# HVSUP_ISOL_Mainboard.net
KiCad netlist of a schematic drawn in Altium Designer
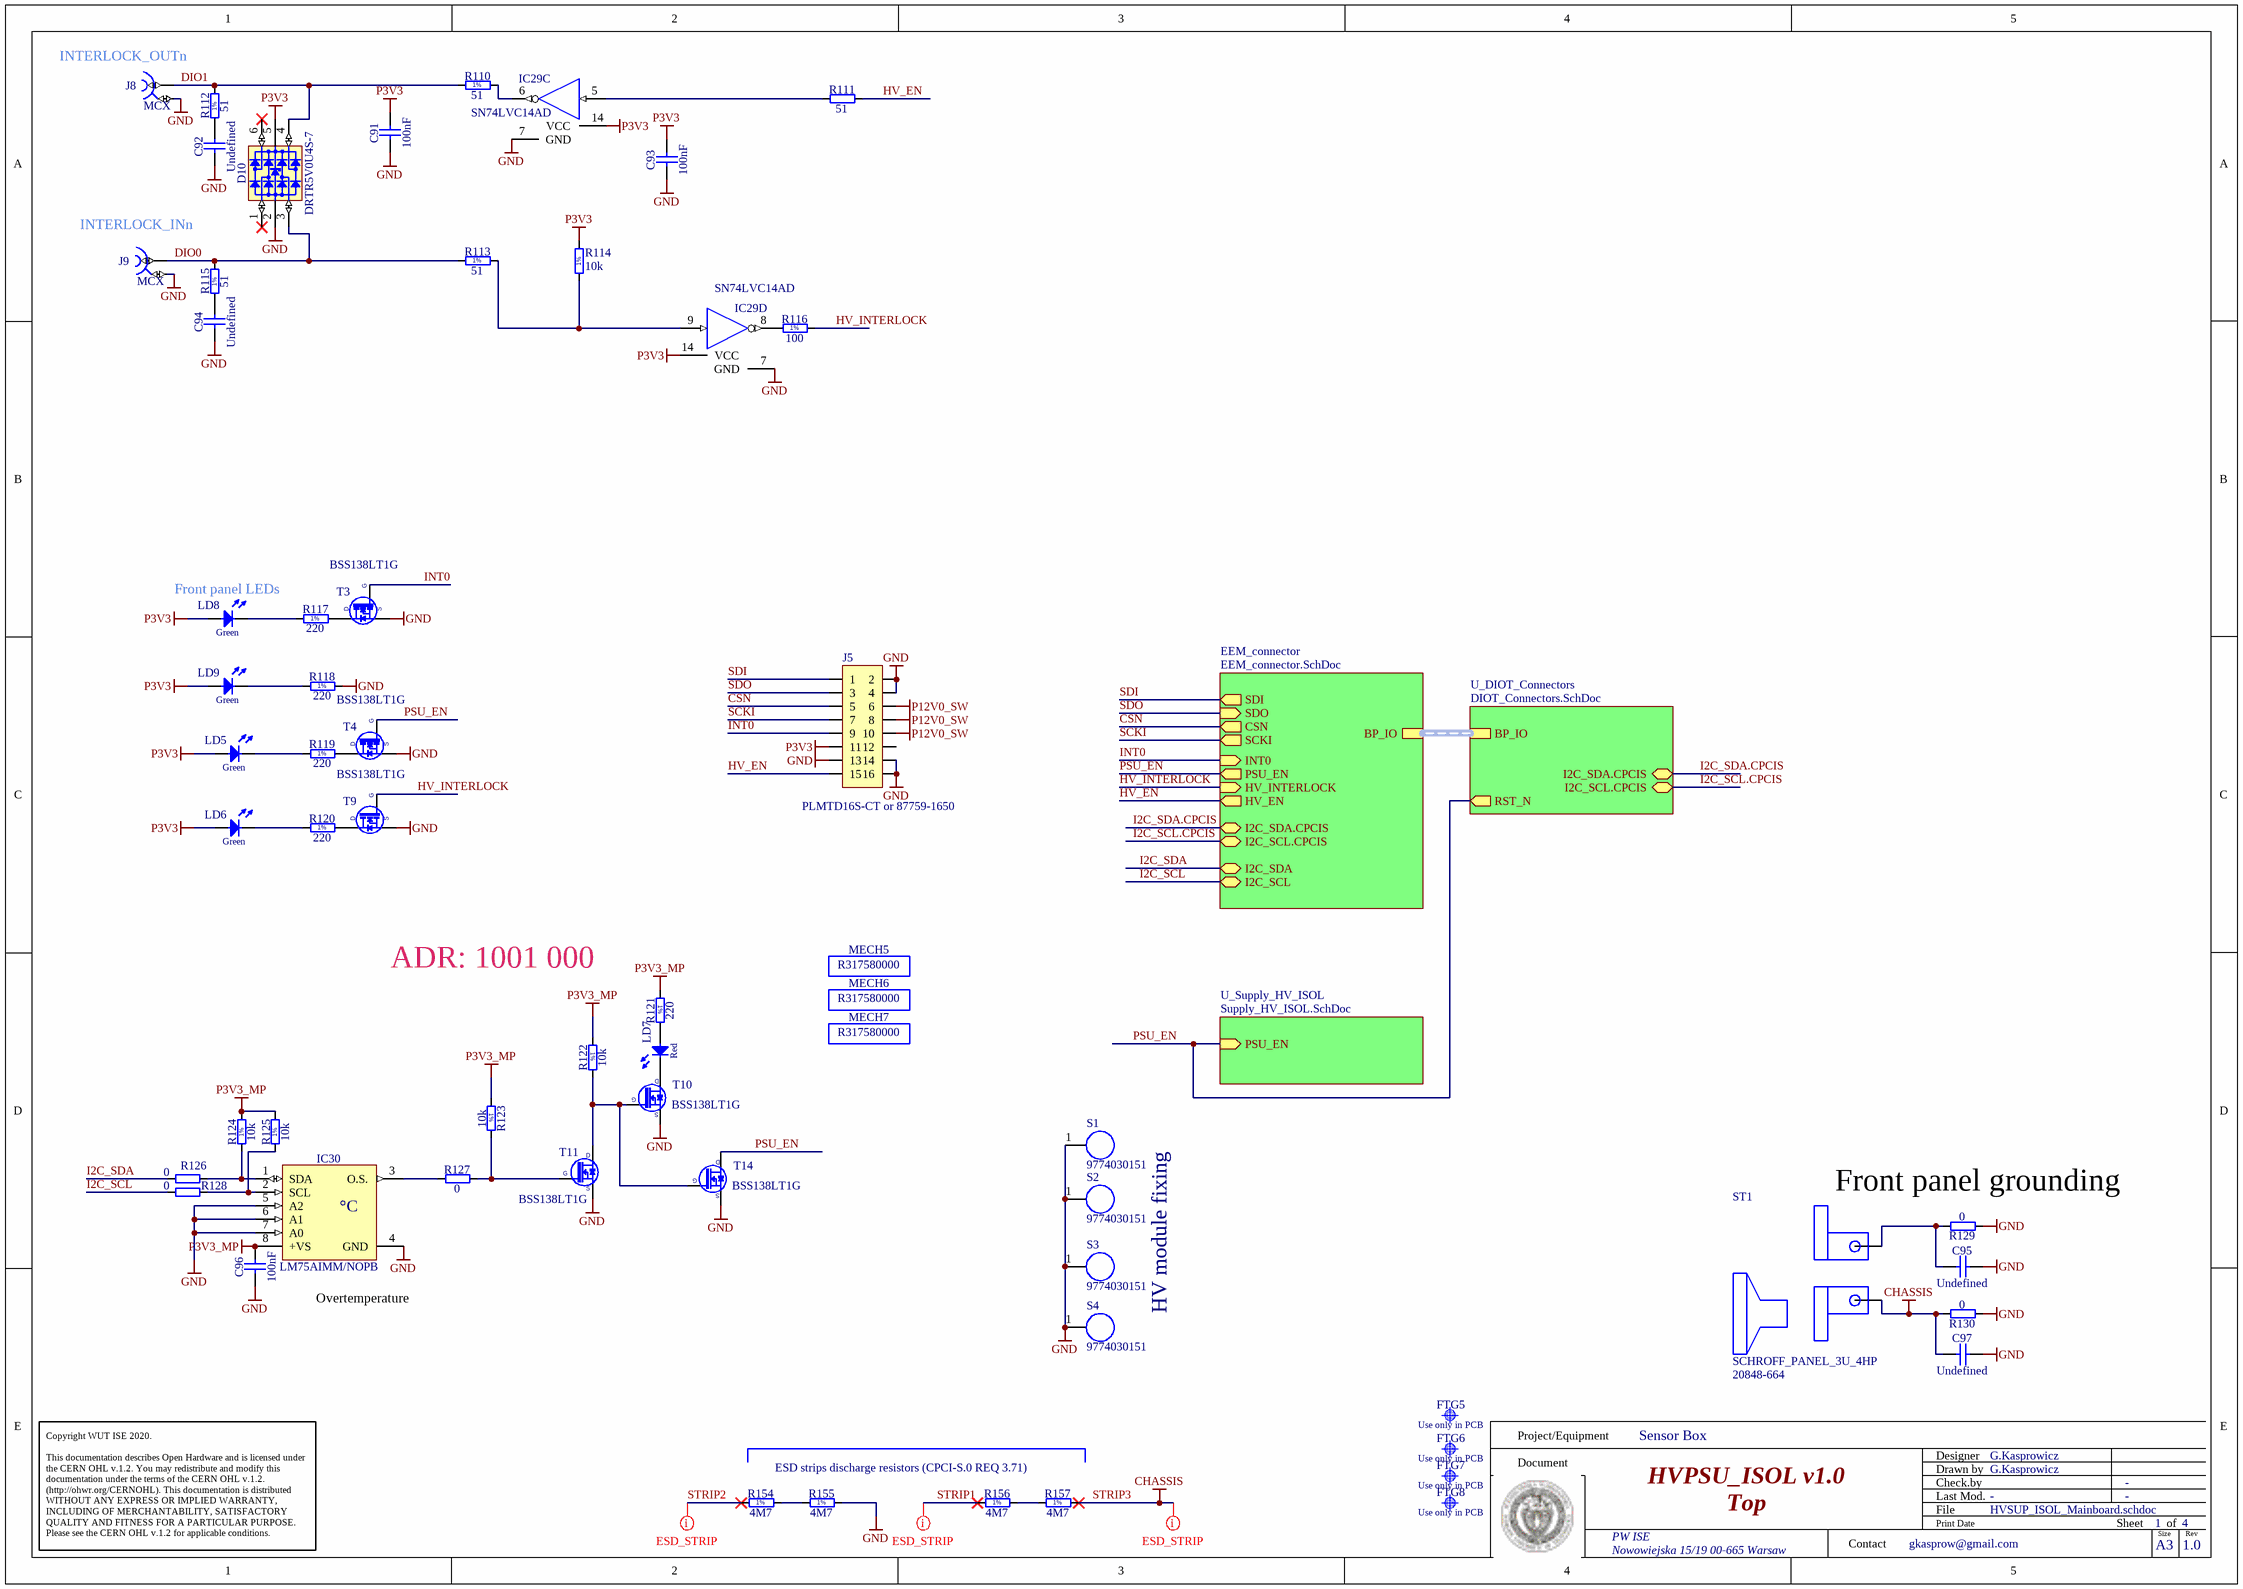
[diagram p0: HVSUP_ISOL_Mainboard.schdoc]

(export (version "E")
  (design (tool "Eeschema 10.0.6"))
  (components
    (comp (ref "C91")
      (value "100nF")
      (footprint "CAPC1005X55N")
      (description "Non-polarised capacitor")
      (fields
        (field (name "PART NUMBER") "CC0402_100NF_16V_10%_X7R")
        (field (name "VOLTAGE") "16V")
        (field (name "AUTHOR") "CERN DEM JLC")
      )
      (libsource (lib "Capacitors") (part "Capacitor - non polarized"))
    )
    (comp (ref "C92")
      (value "Undefined")
      (footprint "CAPC1608X90N")
      (description "Non-polarised capacitor")
      (fields (field (name "PART NUMBER") "CC0603_NO-VALUE") (field (name "AUTHOR") "CERN DEM MR"))
      (libsource (lib "Capacitors") (part "Capacitor - non polarized"))
    )
    (comp (ref "C93")
      (value "100nF")
      (footprint "CAPC1005X55N")
      (description "Non-polarised capacitor")
      (fields
        (field (name "PART NUMBER") "CC0402_100NF_16V_10%_X7R")
        (field (name "VOLTAGE") "16V")
        (field (name "AUTHOR") "CERN DEM JLC")
      )
      (libsource (lib "Capacitors") (part "Capacitor - non polarized"))
    )
    (comp (ref "C94")
      (value "Undefined")
      (footprint "CAPC1608X90N")
      (description "Non-polarised capacitor")
      (fields (field (name "PART NUMBER") "CC0603_NO-VALUE") (field (name "AUTHOR") "CERN DEM MR"))
      (libsource (lib "Capacitors") (part "Capacitor - non polarized"))
    )
    (comp (ref "C95")
      (value "Undefined")
      (footprint "CAPC2012X135N")
      (description "Non-polarised capacitor")
      (fields (field (name "PART NUMBER") "CC0805_NO-VALUE") (field (name "AUTHOR") "CERN DEM JLC"))
      (libsource (lib "Capacitors") (part "Capacitor - non polarized"))
    )
    (comp (ref "C96")
      (value "100nF")
      (footprint "CAPC1005X55N")
      (description "Non-polarised capacitor")
      (fields
        (field (name "PART NUMBER") "CC0402_100NF_16V_10%_X5R")
        (field (name "VOLTAGE") "16V")
        (field (name "AUTHOR") "CERN DEM JLC")
      )
      (libsource (lib "Capacitors") (part "Capacitor - non polarized"))
    )
    (comp (ref "C97")
      (value "Undefined")
      (footprint "CAPC2012X135N")
      (description "Non-polarised capacitor")
      (fields (field (name "PART NUMBER") "CC0805_NO-VALUE") (field (name "AUTHOR") "CERN DEM JLC"))
      (libsource (lib "Capacitors") (part "Capacitor - non polarized"))
    )
    (comp (ref "D10")
      (value "DRTR5V0U4S-7")
      (footprint "SOT65P210X110-6N")
      (description "Integrated Quad Ultra-Low Capacitance ESD Protection")
      (fields (field (name "MANUFACTURER") "DIODES") (field (name "AUTHOR") "GK"))
      (libsource (lib "Diodes") (part "D_TVS_DRTR5V0U4S-7"))
    )
    (comp (ref "FTG5")
      (value "Use only in PCB")
      (footprint "FIDUCIAL_TOP_C100-200")
      (description "Fiducial Target")
      (fields (field (name "PART NUMBER") "FIDUCIAL_TARGET_C100-200") (field (name "AUTHOR") "CERN DEM JLC"))
      (libsource (lib "Eletro-mechanical") (part "Fiducial Target"))
    )
    (comp (ref "FTG6")
      (value "Use only in PCB")
      (footprint "FIDUCIAL_TOP_S100-200")
      (description "Fiducial Target")
      (fields (field (name "PART NUMBER") "FIDUCIAL_TARGET_S100-200") (field (name "AUTHOR") "CERN DEM JLC"))
      (libsource (lib "Eletro-mechanical") (part "Fiducial Target"))
    )
    (comp (ref "FTG7")
      (value "Use only in PCB")
      (footprint "FIDUCIAL_TOP_S100-200")
      (description "Fiducial Target")
      (fields (field (name "PART NUMBER") "FIDUCIAL_TARGET_S100-200") (field (name "AUTHOR") "CERN DEM JLC"))
      (libsource (lib "Eletro-mechanical") (part "Fiducial Target"))
    )
    (comp (ref "FTG8")
      (value "Use only in PCB")
      (footprint "FIDUCIAL_TOP_S100-200")
      (description "Fiducial Target")
      (fields (field (name "PART NUMBER") "FIDUCIAL_TARGET_S100-200") (field (name "AUTHOR") "CERN DEM JLC"))
      (libsource (lib "Eletro-mechanical") (part "Fiducial Target"))
    )
    (comp (ref "IC29")
      (value "SN74LVC14AD")
      (footprint "SOIC127P600X175-14N")
      (description "Hex Schmitt-Trigger Inverter")
      (fields (field (name "MANUFACTURER") "TEXAS INSTRUMENTS") (field (name "AUTHOR") "CERN DEM JMW"))
      (libsource (lib "ICs And Semiconductors") (part "7414"))
    )
    (comp (ref "IC30")
      (value "LM75AIMM/NOPB")
      (footprint "SOP65P490X109-8N")
      (description "Digital Temperature Sensor and Thermal Watchdog with Two-Wire Interface")
      (fields (field (name "MANUFACTURER") "TEXAS INSTRUMENTS") (field (name "AUTHOR") "CERN DEM JLC"))
      (libsource (lib "ICs And Semiconductors") (part "LM75"))
    )
    (comp (ref "J5")
      (value "PLMTD16S-CT or 87759-1650")
      (footprint "87759-1650")
      (description "2mm  dual row rheader (Maritex)")
      (fields (field (name "MANUFACTURER") "Molex") (field (name "MANUFACTURER PART NUMBER") "87759-1650"))
      (libsource (lib "LIBRARY_SCH") (part "CON_2x8 2mm male"))
    )
    (comp (ref "J8")
      (value "MCX")
      (footprint "AMPHENOL_919-383J-51A")
      (fields
        (field (name "PART NUMBER") "AMPHENOL_919-383J-51A")
        (field (name "MANUFACTURER") "AMPHENOL")
        (field (name "MANUFACTURER PART NUMBER") "919-383J-51A")
        (field (name "AUTHOR") "CERN DEM BC")
      )
      (libsource (lib "Connectors") (part "Coax_1Female_1Shield"))
    )
    (comp (ref "J9")
      (value "MCX")
      (footprint "AMPHENOL_919-383J-51A")
      (fields
        (field (name "PART NUMBER") "AMPHENOL_919-383J-51A")
        (field (name "MANUFACTURER") "AMPHENOL")
        (field (name "MANUFACTURER PART NUMBER") "919-383J-51A")
        (field (name "AUTHOR") "CERN DEM BC")
      )
      (libsource (lib "Connectors") (part "Coax_1Female_1Shield"))
    )
    (comp (ref "LD5")
      (value "Green")
      (footprint "LED_DIALIGHT_555-230")
      (description "LED Green 1C 2A")
      (fields
        (field (name "PART NUMBER") "LED_DIALIGHT_555-2301F")
        (field (name "MANUFACTURER") "DIALIGHT")
        (field (name "AUTHOR") "CERN DEM JMW")
      )
      (libsource (lib "ICs And Semiconductors") (part "LED Green 1C 2A"))
    )
    (comp (ref "LD6")
      (value "Green")
      (footprint "LED_DIALIGHT_555-230")
      (description "LED Green 1C 2A")
      (fields
        (field (name "PART NUMBER") "LED_DIALIGHT_555-2301F")
        (field (name "MANUFACTURER") "DIALIGHT")
        (field (name "AUTHOR") "CERN DEM JMW")
      )
      (libsource (lib "ICs And Semiconductors") (part "LED Green 1C 2A"))
    )
    (comp (ref "LD7")
      (value "Red")
      (footprint "LED_DIALIGHT_555-200")
      (description "LED Red 1C 2A")
      (fields
        (field (name "PART NUMBER") "LED_DIALIGHT_555-2001F")
        (field (name "MANUFACTURER") "DIALIGHT")
        (field (name "AUTHOR") "CERN DEM JMW")
      )
      (libsource (lib "ICs And Semiconductors") (part "LED Red 1C 2A"))
    )
    (comp (ref "LD8")
      (value "Green")
      (footprint "LED_DIALIGHT_555-230")
      (description "LED Green 1C 2A")
      (fields
        (field (name "PART NUMBER") "LED_DIALIGHT_555-2301F")
        (field (name "MANUFACTURER") "DIALIGHT")
        (field (name "AUTHOR") "CERN DEM JMW")
      )
      (libsource (lib "ICs And Semiconductors") (part "LED Green 1C 2A"))
    )
    (comp (ref "LD9")
      (value "Green")
      (footprint "LED_DIALIGHT_555-230")
      (description "LED Green 1C 2A")
      (fields
        (field (name "PART NUMBER") "LED_DIALIGHT_555-2301F")
        (field (name "MANUFACTURER") "DIALIGHT")
        (field (name "AUTHOR") "CERN DEM JMW")
      )
      (libsource (lib "ICs And Semiconductors") (part "LED Green 1C 2A"))
    )
    (comp (ref "MECH5")
      (value "R317580000")
      (footprint "GENERIC_MECH")
      (description "SHV connector")
      (fields (field (name "MANUFACTURER") "Radiall") (field (name "AUTHOR") "GK"))
      (libsource (lib "Mechanical") (part "Generic_mechanical"))
    )
    (comp (ref "MECH6")
      (value "R317580000")
      (footprint "GENERIC_MECH")
      (description "SHV connector")
      (fields (field (name "MANUFACTURER") "Radiall") (field (name "AUTHOR") "GK"))
      (libsource (lib "Mechanical") (part "Generic_mechanical"))
    )
    (comp (ref "MECH7")
      (value "R317580000")
      (footprint "GENERIC_MECH")
      (description "SHV connector")
      (fields (field (name "MANUFACTURER") "Radiall") (field (name "AUTHOR") "GK"))
      (libsource (lib "Mechanical") (part "Generic_mechanical"))
    )
    (comp (ref "R110")
      (value "51")
      (footprint "RESC1005X40N")
      (description "Resistor - 1%")
      (fields
        (field (name "PART NUMBER") "R0402_51R_1%_0.0625W_100PPM")
        (field (name "POWER") "0.0625W")
        (field (name "AUTHOR") "CERN DEM JLC")
      )
      (libsource (lib "Resistors") (part "Resistor - 1%"))
    )
    (comp (ref "R111")
      (value "51")
      (footprint "RESC1005X40N")
      (description "Resistor - 1%")
      (fields
        (field (name "PART NUMBER") "R0402_51R_1%_0.0625W_100PPM")
        (field (name "POWER") "0.0625W")
        (field (name "AUTHOR") "CERN DEM JLC")
      )
      (libsource (lib "Resistors") (part "Resistor - 1%"))
    )
    (comp (ref "R112")
      (value "51")
      (footprint "RESC1005X40N")
      (description "Resistor - 1%")
      (fields
        (field (name "PART NUMBER") "R0402_51R_1%_0.0625W_100PPM")
        (field (name "POWER") "0.0625W")
        (field (name "AUTHOR") "CERN DEM JLC")
      )
      (libsource (lib "Resistors") (part "Resistor - 1%"))
    )
    (comp (ref "R113")
      (value "51")
      (footprint "RESC1005X40N")
      (description "Resistor - 1%")
      (fields
        (field (name "PART NUMBER") "R0402_51R_1%_0.0625W_100PPM")
        (field (name "POWER") "0.0625W")
        (field (name "AUTHOR") "CERN DEM JLC")
      )
      (libsource (lib "Resistors") (part "Resistor - 1%"))
    )
    (comp (ref "R114")
      (value "10k")
      (footprint "RESC1005X40N")
      (description "Resistor - 1%")
      (fields
        (field (name "PART NUMBER") "R0402_10K_1%_0.0625W_100PPM")
        (field (name "POWER") "0.0625W")
        (field (name "AUTHOR") "CERN DEM JLC")
      )
      (libsource (lib "Resistors") (part "Resistor - 1%"))
    )
    (comp (ref "R115")
      (value "51")
      (footprint "RESC1005X40N")
      (description "Resistor - 1%")
      (fields
        (field (name "PART NUMBER") "R0402_51R_1%_0.0625W_100PPM")
        (field (name "POWER") "0.0625W")
        (field (name "AUTHOR") "CERN DEM JLC")
      )
      (libsource (lib "Resistors") (part "Resistor - 1%"))
    )
    (comp (ref "R116")
      (value "100")
      (footprint "RESC1005X40N")
      (description "Resistor - 1%")
      (fields
        (field (name "PART NUMBER") "R0402_100R_1%_0.0625W_100PPM")
        (field (name "POWER") "0.0625W")
        (field (name "AUTHOR") "CERN DEM JLC")
      )
      (libsource (lib "Resistors") (part "Resistor - 1%"))
    )
    (comp (ref "R117")
      (value "220")
      (footprint "RESC1608X55N")
      (description "Resistor - 1%")
      (fields
        (field (name "PART NUMBER") "R0603_220R_1%_0.1W_100PPM")
        (field (name "POWER") "0.1W")
        (field (name "AUTHOR") "CERN DEM JLC")
      )
      (libsource (lib "Resistors") (part "Resistor - 1%"))
    )
    (comp (ref "R118")
      (value "220")
      (footprint "RESC1608X55N")
      (description "Resistor - 1%")
      (fields
        (field (name "PART NUMBER") "R0603_220R_1%_0.1W_100PPM")
        (field (name "POWER") "0.1W")
        (field (name "AUTHOR") "CERN DEM JLC")
      )
      (libsource (lib "Resistors") (part "Resistor - 1%"))
    )
    (comp (ref "R119")
      (value "220")
      (footprint "RESC1608X55N")
      (description "Resistor - 1%")
      (fields
        (field (name "PART NUMBER") "R0603_220R_1%_0.1W_100PPM")
        (field (name "POWER") "0.1W")
        (field (name "AUTHOR") "CERN DEM JLC")
      )
      (libsource (lib "Resistors") (part "Resistor - 1%"))
    )
    (comp (ref "R120")
      (value "220")
      (footprint "RESC1608X55N")
      (description "Resistor - 1%")
      (fields
        (field (name "PART NUMBER") "R0603_220R_1%_0.1W_100PPM")
        (field (name "POWER") "0.1W")
        (field (name "AUTHOR") "CERN DEM JLC")
      )
      (libsource (lib "Resistors") (part "Resistor - 1%"))
    )
    (comp (ref "R121")
      (value "220")
      (footprint "RESC1608X55N")
      (description "Resistor - 1%")
      (fields
        (field (name "PART NUMBER") "R0603_220R_1%_0.1W_100PPM")
        (field (name "POWER") "0.1W")
        (field (name "AUTHOR") "CERN DEM JLC")
      )
      (libsource (lib "Resistors") (part "Resistor - 1%"))
    )
    (comp (ref "R122")
      (value "10k")
      (footprint "RESC1005X40N")
      (description "Resistor - 1%")
      (fields
        (field (name "PART NUMBER") "R0402_10K_1%_0.0625W_100PPM")
        (field (name "POWER") "0.0625W")
        (field (name "AUTHOR") "CERN DEM JLC")
      )
      (libsource (lib "Resistors") (part "Resistor - 1%"))
    )
    (comp (ref "R123")
      (value "10k")
      (footprint "RESC1005X40N")
      (description "Resistor - 1%")
      (fields
        (field (name "PART NUMBER") "R0402_10K_1%_0.0625W_100PPM")
        (field (name "POWER") "0.0625W")
        (field (name "AUTHOR") "CERN DEM JLC")
      )
      (libsource (lib "Resistors") (part "Resistor - 1%"))
    )
    (comp (ref "R124")
      (value "10k")
      (footprint "RESC1005X40N")
      (description "Resistor - 1%")
      (fields
        (field (name "PART NUMBER") "R0402_10K_1%_0.0625W_100PPM")
        (field (name "POWER") "0.0625W")
        (field (name "AUTHOR") "CERN DEM JLC")
      )
      (libsource (lib "Resistors") (part "Resistor - 1%"))
    )
    (comp (ref "R125")
      (value "10k")
      (footprint "RESC1005X40N")
      (description "Resistor - 1%")
      (fields
        (field (name "PART NUMBER") "R0402_10K_1%_0.0625W_100PPM")
        (field (name "POWER") "0.0625W")
        (field (name "AUTHOR") "CERN DEM JLC")
      )
      (libsource (lib "Resistors") (part "Resistor - 1%"))
    )
    (comp (ref "R126")
      (value "0")
      (footprint "RESC1005X40N")
      (description "Resistor")
      (fields
        (field (name "PART NUMBER") "R0402_0R_JUMPER")
        (field (name "MANUFACTURER") "GENERIC")
        (field (name "AUTHOR") "CERN DEM JLC")
      )
      (libsource (lib "Resistors") (part "Resistor"))
    )
    (comp (ref "R127")
      (value "0")
      (footprint "RESC1005X40N")
      (description "Resistor")
      (fields
        (field (name "PART NUMBER") "R0402_0R_JUMPER")
        (field (name "MANUFACTURER") "GENERIC")
        (field (name "AUTHOR") "CERN DEM JLC")
      )
      (libsource (lib "Resistors") (part "Resistor"))
    )
    (comp (ref "R128")
      (value "0")
      (footprint "RESC1005X40N")
      (description "Resistor")
      (fields
        (field (name "PART NUMBER") "R0402_0R_JUMPER")
        (field (name "MANUFACTURER") "GENERIC")
        (field (name "AUTHOR") "CERN DEM JLC")
      )
      (libsource (lib "Resistors") (part "Resistor"))
    )
    (comp (ref "R129")
      (value "0")
      (footprint "RESC1608X55N")
      (description "Resistor")
      (fields
        (field (name "PART NUMBER") "R0603_0R_JUMPER")
        (field (name "MANUFACTURER") "GENERIC")
        (field (name "AUTHOR") "CERN DEM JLC")
      )
      (libsource (lib "Resistors") (part "Resistor"))
    )
    (comp (ref "R130")
      (value "0")
      (footprint "RESC1608X55N")
      (description "Resistor")
      (fields
        (field (name "PART NUMBER") "R0603_0R_JUMPER")
        (field (name "MANUFACTURER") "GENERIC")
        (field (name "AUTHOR") "CERN DEM JLC")
      )
      (libsource (lib "Resistors") (part "Resistor"))
    )
    (comp (ref "R154")
      (value "4M7")
      (footprint "RESC2113X55N")
      (description "Resistor - 1%")
      (fields
        (field (name "PART NUMBER") "R0805_4M7_1%_0.125W_100PPM_VISHAY_CRCW e3")
        (field (name "POWER") "0.125W")
        (field (name "AUTHOR") "CERN DEM BR")
      )
      (libsource (lib "Resistors") (part "Resistor - 1%"))
    )
    (comp (ref "R155")
      (value "4M7")
      (footprint "RESC2113X55N")
      (description "Resistor - 1%")
      (fields
        (field (name "PART NUMBER") "R0805_4M7_1%_0.125W_100PPM_VISHAY_CRCW e3")
        (field (name "POWER") "0.125W")
        (field (name "AUTHOR") "CERN DEM BR")
      )
      (libsource (lib "Resistors") (part "Resistor - 1%"))
    )
    (comp (ref "R156")
      (value "4M7")
      (footprint "RESC2113X55N")
      (description "Resistor - 1%")
      (fields
        (field (name "PART NUMBER") "R0805_4M7_1%_0.125W_100PPM_VISHAY_CRCW e3")
        (field (name "POWER") "0.125W")
        (field (name "AUTHOR") "CERN DEM BR")
      )
      (libsource (lib "Resistors") (part "Resistor - 1%"))
    )
    (comp (ref "R157")
      (value "4M7")
      (footprint "RESC2113X55N")
      (description "Resistor - 1%")
      (fields
        (field (name "PART NUMBER") "R0805_4M7_1%_0.125W_100PPM_VISHAY_CRCW e3")
        (field (name "POWER") "0.125W")
        (field (name "AUTHOR") "CERN DEM BR")
      )
      (libsource (lib "Resistors") (part "Resistor - 1%"))
    )
    (comp (ref "S1")
      (value "9774030151")
      (footprint "9774030151")
      (description "WA-SMSI SMD Steel Spacer with internal Thread")
      (fields (field (name "MANUFACTURER") "Wurth Elektronik") (field (name "CREATED BY") "Baojun Chen"))
      (libsource (lib "Altium_SMSI_SMT_STEEL_SPACER_M2_5_THREAD_INTERNAL_rev15a") (part "WA-SMSI,  9774030151"))
    )
    (comp (ref "S2")
      (value "9774030151")
      (footprint "9774030151")
      (description "WA-SMSI SMD Steel Spacer with internal Thread")
      (fields (field (name "MANUFACTURER") "Wurth Elektronik") (field (name "CREATED BY") "Baojun Chen"))
      (libsource (lib "Altium_SMSI_SMT_STEEL_SPACER_M2_5_THREAD_INTERNAL_rev15a") (part "WA-SMSI,  9774030151"))
    )
    (comp (ref "S3")
      (value "9774030151")
      (footprint "9774030151")
      (description "WA-SMSI SMD Steel Spacer with internal Thread")
      (fields (field (name "MANUFACTURER") "Wurth Elektronik") (field (name "CREATED BY") "Baojun Chen"))
      (libsource (lib "Altium_SMSI_SMT_STEEL_SPACER_M2_5_THREAD_INTERNAL_rev15a") (part "WA-SMSI,  9774030151"))
    )
    (comp (ref "S4")
      (value "9774030151")
      (footprint "9774030151")
      (description "WA-SMSI SMD Steel Spacer with internal Thread")
      (fields (field (name "MANUFACTURER") "Wurth Elektronik") (field (name "CREATED BY") "Baojun Chen"))
      (libsource (lib "Altium_SMSI_SMT_STEEL_SPACER_M2_5_THREAD_INTERNAL_rev15a") (part "WA-SMSI,  9774030151"))
    )
    (comp (ref "ST1")
      (value "SCHROFF_PANEL_3U_4HP")
      (footprint "SCHROFF_PANEL_3HP_4U")
      (description "Schroff 3HP 4U EUROCARD Panel Kit")
      (fields
        (field (name "MANUFACTURER") "Schroff")
        (field (name "MANUFACTURER PART NUMBER") "20818-017")
        (field (name "MANUFACTURER PART NUMBER 2") "20848-664")
      )
      (libsource (lib "Mechanical") (part "SCHROFF_PANEL_3U_4HP"))
    )
    (comp (ref "T3")
      (value "BSS138LT1G")
      (footprint "SOT95P240X110-3N")
      (description "N-CHANNEL MOSFET WITH DIODE")
      (fields (field (name "MANUFACTURER") "ON SEMICONDUCTOR") (field (name "AUTHOR") "CERN DEM JLC"))
      (libsource (lib "ICs And Semiconductors") (part "N-MOSFET-D 1G 2S 3D"))
    )
    (comp (ref "T4")
      (value "BSS138LT1G")
      (footprint "SOT95P240X110-3N")
      (description "N-CHANNEL MOSFET WITH DIODE")
      (fields (field (name "MANUFACTURER") "ON SEMICONDUCTOR") (field (name "AUTHOR") "CERN DEM JLC"))
      (libsource (lib "ICs And Semiconductors") (part "N-MOSFET-D 1G 2S 3D"))
    )
    (comp (ref "T9")
      (value "BSS138LT1G")
      (footprint "SOT95P240X110-3N")
      (description "N-CHANNEL MOSFET WITH DIODE")
      (fields (field (name "MANUFACTURER") "ON SEMICONDUCTOR") (field (name "AUTHOR") "CERN DEM JLC"))
      (libsource (lib "ICs And Semiconductors") (part "N-MOSFET-D 1G 2S 3D"))
    )
    (comp (ref "T10")
      (value "BSS138LT1G")
      (footprint "SOT95P240X110-3N")
      (description "N-CHANNEL MOSFET WITH DIODE")
      (fields (field (name "MANUFACTURER") "ON SEMICONDUCTOR") (field (name "AUTHOR") "CERN DEM JLC"))
      (libsource (lib "") (part "N-MOSFET-D 1G 2S 3D_1"))
    )
    (comp (ref "T11")
      (value "BSS138LT1G")
      (footprint "SOT95P240X110-3N")
      (description "N-CHANNEL MOSFET WITH DIODE")
      (fields (field (name "MANUFACTURER") "ON SEMICONDUCTOR") (field (name "AUTHOR") "CERN DEM JLC"))
      (libsource (lib "") (part "N-MOSFET-D 1G 2S 3D_2"))
    )
    (comp (ref "T14")
      (value "BSS138LT1G")
      (footprint "SOT95P240X110-3N")
      (description "N-CHANNEL MOSFET WITH DIODE")
      (fields (field (name "MANUFACTURER") "ON SEMICONDUCTOR") (field (name "AUTHOR") "CERN DEM JLC"))
      (libsource (lib "") (part "N-MOSFET-D 1G 2S 3D_1"))
    )
  )
  (nets
    (net (code "2") (name "/CSN") (class "Default")
      (node (ref "J5") (pin "5") (pinfunction "5_5") (pintype "passive"))
    )
    (net (code "3") (name "/DIO0") (class "Default")
      (node (ref "D10") (pin "3") (pinfunction "I/O2_3") (pintype "bidirectional"))
      (node (ref "J9") (pin "1") (pinfunction "1_1") (pintype "bidirectional"))
      (node (ref "R113") (pin "1") (pinfunction "1_1") (pintype "passive"))
      (node (ref "R115") (pin "2") (pinfunction "2_2") (pintype "passive"))
    )
    (net (code "4") (name "/DIO1") (class "Default")
      (node (ref "D10") (pin "4") (pinfunction "I/O3_4") (pintype "bidirectional"))
      (node (ref "J8") (pin "1") (pinfunction "1_1") (pintype "bidirectional"))
      (node (ref "R110") (pin "1") (pinfunction "1_1") (pintype "passive"))
      (node (ref "R112") (pin "2") (pinfunction "2_2") (pintype "passive"))
    )
    (net (code "5") (name "/HV_EN") (class "Default")
      (node (ref "J5") (pin "15") (pinfunction "15_15") (pintype "passive"))
      (node (ref "R111") (pin "2") (pinfunction "2_2") (pintype "passive"))
    )
    (net (code "6") (name "/HV_INTERLOCK") (class "Default")
      (node (ref "R116") (pin "2") (pinfunction "2_2") (pintype "passive"))
      (node (ref "T9") (pin "1") (pinfunction "G_1") (pintype "passive"))
    )
    (net (code "7") (name "/I2C_SCL") (class "Default")
      (node (ref "R128") (pin "1") (pinfunction "1_1") (pintype "passive"))
    )
    (net (code "9") (name "/I2C_SDA") (class "Default")
      (node (ref "R126") (pin "1") (pinfunction "1_1") (pintype "passive"))
    )
    (net (code "11") (name "/INT0") (class "Default")
      (node (ref "J5") (pin "9") (pinfunction "9_9") (pintype "passive"))
      (node (ref "T3") (pin "1") (pinfunction "G_1") (pintype "passive"))
    )
    (net (code "12") (name "/PSU_EN") (class "Default")
      (node (ref "T14") (pin "3") (pinfunction "D_3") (pintype "passive"))
      (node (ref "T4") (pin "1") (pinfunction "G_1") (pintype "passive"))
    )
    (net (code "13") (name "/SCKI") (class "Default")
      (node (ref "J5") (pin "7") (pinfunction "7_7") (pintype "passive"))
    )
    (net (code "14") (name "/SDI") (class "Default")
      (node (ref "J5") (pin "1") (pinfunction "1_1") (pintype "passive"))
    )
    (net (code "15") (name "/SDO") (class "Default")
      (node (ref "J5") (pin "3") (pinfunction "3_3") (pintype "passive"))
    )
    (net (code "16") (name "/STRIP1") (class "Default")
      (node (ref "R156") (pin "1") (pinfunction "1_1") (pintype "passive+no_connect"))
    )
    (net (code "17") (name "/STRIP2") (class "Default")
      (node (ref "R154") (pin "1") (pinfunction "1_1") (pintype "passive+no_connect"))
    )
    (net (code "18") (name "CHASSIS") (class "Default")
      (node (ref "C97") (pin "1") (pinfunction "1_1") (pintype "passive"))
      (node (ref "R130") (pin "2") (pinfunction "2_2") (pintype "passive"))
      (node (ref "R157") (pin "2") (pinfunction "2_2") (pintype "passive"))
      (node (ref "ST1") (pin "0") (pinfunction "0_0") (pintype "passive"))
    )
    (net (code "19") (name "GND") (class "Default")
      (node (ref "C91") (pin "1") (pinfunction "1_1") (pintype "passive"))
      (node (ref "C92") (pin "1") (pinfunction "1_1") (pintype "passive"))
      (node (ref "C93") (pin "1") (pinfunction "1_1") (pintype "passive"))
      (node (ref "C94") (pin "1") (pinfunction "1_1") (pintype "passive"))
      (node (ref "C95") (pin "2") (pinfunction "2_2") (pintype "passive"))
      (node (ref "C96") (pin "1") (pinfunction "1_1") (pintype "passive"))
      (node (ref "C97") (pin "2") (pinfunction "2_2") (pintype "passive"))
      (node (ref "D10") (pin "2") (pinfunction "GND_2") (pintype "power_in"))
      (node (ref "IC29") (pin "7") (pinfunction "GND_7") (pintype "power_in"))
      (node (ref "IC30") (pin "4") (pinfunction "GND_4") (pintype "power_in"))
      (node (ref "IC30") (pin "5") (pinfunction "A2_5") (pintype "input"))
      (node (ref "IC30") (pin "6") (pinfunction "A1_6") (pintype "input"))
      (node (ref "IC30") (pin "7") (pinfunction "A0_7") (pintype "input"))
      (node (ref "J5") (pin "13") (pinfunction "13_13") (pintype "passive"))
      (node (ref "J5") (pin "14") (pinfunction "14_14") (pintype "passive"))
      (node (ref "J5") (pin "16") (pinfunction "16_16") (pintype "passive"))
      (node (ref "J5") (pin "2") (pinfunction "2_2") (pintype "passive"))
      (node (ref "J5") (pin "4") (pinfunction "4_4") (pintype "passive"))
      (node (ref "J8") (pin "2") (pinfunction "2_2") (pintype "bidirectional"))
      (node (ref "J9") (pin "2") (pinfunction "2_2") (pintype "bidirectional"))
      (node (ref "R118") (pin "2") (pinfunction "2_2") (pintype "passive"))
      (node (ref "R129") (pin "1") (pinfunction "1_1") (pintype "passive"))
      (node (ref "R130") (pin "1") (pinfunction "1_1") (pintype "passive"))
      (node (ref "R155") (pin "2") (pinfunction "2_2") (pintype "passive"))
      (node (ref "S1") (pin "1") (pinfunction "1_1") (pintype "passive"))
      (node (ref "S2") (pin "1") (pinfunction "1_1") (pintype "passive"))
      (node (ref "S3") (pin "1") (pinfunction "1_1") (pintype "passive"))
      (node (ref "S4") (pin "1") (pinfunction "1_1") (pintype "passive"))
      (node (ref "T10") (pin "2") (pinfunction "S_2") (pintype "passive"))
      (node (ref "T11") (pin "2") (pinfunction "S_2") (pintype "passive"))
      (node (ref "T14") (pin "2") (pinfunction "S_2") (pintype "passive"))
      (node (ref "T3") (pin "2") (pinfunction "S_2") (pintype "passive"))
      (node (ref "T4") (pin "2") (pinfunction "S_2") (pintype "passive"))
      (node (ref "T9") (pin "2") (pinfunction "S_2") (pintype "passive"))
    )
    (net (code "20") (name "Net-(C92-Pad2)") (class "Default")
      (node (ref "C92") (pin "2") (pinfunction "2_2") (pintype "passive"))
      (node (ref "R112") (pin "1") (pinfunction "1_1") (pintype "passive"))
    )
    (net (code "21") (name "Net-(C94-Pad2)") (class "Default")
      (node (ref "C94") (pin "2") (pinfunction "2_2") (pintype "passive"))
      (node (ref "R115") (pin "1") (pinfunction "1_1") (pintype "passive"))
    )
    (net (code "22") (name "Net-(C95-Pad1)") (class "Default")
      (node (ref "C95") (pin "1") (pinfunction "1_1") (pintype "passive"))
      (node (ref "R129") (pin "2") (pinfunction "2_2") (pintype "passive"))
      (node (ref "ST1") (pin "1") (pinfunction "1_1") (pintype "passive"))
    )
    (net (code "23") (name "Net-(IC29C-IN)") (class "Default")
      (node (ref "IC29") (pin "5") (pinfunction "IN_5") (pintype "input"))
      (node (ref "R111") (pin "1") (pinfunction "1_1") (pintype "passive"))
    )
    (net (code "24") (name "Net-(IC29C-OUT)") (class "Default")
      (node (ref "IC29") (pin "6") (pinfunction "OUT_6") (pintype "output"))
      (node (ref "R110") (pin "2") (pinfunction "2_2") (pintype "passive"))
    )
    (net (code "25") (name "Net-(IC29D-IN)") (class "Default")
      (node (ref "IC29") (pin "9") (pinfunction "IN_9") (pintype "input"))
      (node (ref "R113") (pin "2") (pinfunction "2_2") (pintype "passive"))
      (node (ref "R114") (pin "1") (pinfunction "1_1") (pintype "passive"))
    )
    (net (code "26") (name "Net-(IC29D-OUT)") (class "Default")
      (node (ref "IC29") (pin "8") (pinfunction "OUT_8") (pintype "output"))
      (node (ref "R116") (pin "1") (pinfunction "1_1") (pintype "passive"))
    )
    (net (code "27") (name "Net-(IC30-O.S.)") (class "Default")
      (node (ref "IC30") (pin "3") (pinfunction "O.S._3") (pintype "output"))
      (node (ref "R127") (pin "1") (pinfunction "1_1") (pintype "passive"))
    )
    (net (code "28") (name "Net-(IC30-SCL)") (class "Default")
      (node (ref "IC30") (pin "2") (pinfunction "SCL_2") (pintype "input"))
      (node (ref "R125") (pin "1") (pinfunction "1_1") (pintype "passive"))
      (node (ref "R128") (pin "2") (pinfunction "2_2") (pintype "passive"))
    )
    (net (code "29") (name "Net-(IC30-SDA)") (class "Default")
      (node (ref "IC30") (pin "1") (pinfunction "SDA_1") (pintype "bidirectional"))
      (node (ref "R124") (pin "1") (pinfunction "1_1") (pintype "passive"))
      (node (ref "R126") (pin "2") (pinfunction "2_2") (pintype "passive"))
    )
    (net (code "30") (name "Net-(LD5-C)") (class "Default")
      (node (ref "LD5") (pin "1") (pinfunction "C_1") (pintype "passive"))
      (node (ref "R119") (pin "1") (pinfunction "1_1") (pintype "passive"))
    )
    (net (code "31") (name "Net-(LD6-C)") (class "Default")
      (node (ref "LD6") (pin "1") (pinfunction "C_1") (pintype "passive"))
      (node (ref "R120") (pin "1") (pinfunction "1_1") (pintype "passive"))
    )
    (net (code "32") (name "Net-(LD7-A)") (class "Default")
      (node (ref "LD7") (pin "2") (pinfunction "A_2") (pintype "passive"))
      (node (ref "R121") (pin "2") (pinfunction "2_2") (pintype "passive"))
    )
    (net (code "33") (name "Net-(LD7-C)") (class "Default")
      (node (ref "LD7") (pin "1") (pinfunction "C_1") (pintype "passive"))
      (node (ref "T10") (pin "3") (pinfunction "D_3") (pintype "passive"))
    )
    (net (code "34") (name "Net-(LD8-C)") (class "Default")
      (node (ref "LD8") (pin "1") (pinfunction "C_1") (pintype "passive"))
      (node (ref "R117") (pin "1") (pinfunction "1_1") (pintype "passive"))
    )
    (net (code "35") (name "Net-(LD9-C)") (class "Default")
      (node (ref "LD9") (pin "1") (pinfunction "C_1") (pintype "passive"))
      (node (ref "R118") (pin "1") (pinfunction "1_1") (pintype "passive"))
    )
    (net (code "36") (name "Net-(R154-Pad2)") (class "Default")
      (node (ref "R154") (pin "2") (pinfunction "2_2") (pintype "passive"))
      (node (ref "R155") (pin "1") (pinfunction "1_1") (pintype "passive"))
    )
    (net (code "37") (name "Net-(R156-Pad2)") (class "Default")
      (node (ref "R156") (pin "2") (pinfunction "2_2") (pintype "passive"))
      (node (ref "R157") (pin "1") (pinfunction "1_1") (pintype "passive"))
    )
    (net (code "38") (name "Net-(T3-D)") (class "Default")
      (node (ref "R117") (pin "2") (pinfunction "2_2") (pintype "passive"))
      (node (ref "T3") (pin "3") (pinfunction "D_3") (pintype "passive"))
    )
    (net (code "39") (name "Net-(T4-D)") (class "Default")
      (node (ref "R119") (pin "2") (pinfunction "2_2") (pintype "passive"))
      (node (ref "T4") (pin "3") (pinfunction "D_3") (pintype "passive"))
    )
    (net (code "40") (name "Net-(T9-D)") (class "Default")
      (node (ref "R120") (pin "2") (pinfunction "2_2") (pintype "passive"))
      (node (ref "T9") (pin "3") (pinfunction "D_3") (pintype "passive"))
    )
    (net (code "41") (name "Net-(T10-G)") (class "Default")
      (node (ref "R122") (pin "2") (pinfunction "2_2") (pintype "passive"))
      (node (ref "T10") (pin "1") (pinfunction "G_1") (pintype "passive"))
      (node (ref "T11") (pin "3") (pinfunction "D_3") (pintype "passive"))
      (node (ref "T14") (pin "1") (pinfunction "G_1") (pintype "passive"))
    )
    (net (code "42") (name "Net-(T11-G)") (class "Default")
      (node (ref "R123") (pin "2") (pinfunction "2_2") (pintype "passive"))
      (node (ref "R127") (pin "2") (pinfunction "2_2") (pintype "passive"))
      (node (ref "T11") (pin "1") (pinfunction "G_1") (pintype "passive"))
    )
    (net (code "43") (name "P3V3") (class "Default")
      (node (ref "C91") (pin "2") (pinfunction "2_2") (pintype "passive"))
      (node (ref "C93") (pin "2") (pinfunction "2_2") (pintype "passive"))
      (node (ref "D10") (pin "5") (pinfunction "VBUS_5") (pintype "power_in"))
      (node (ref "IC29") (pin "14") (pinfunction "VCC_14") (pintype "power_in"))
      (node (ref "J5") (pin "11") (pinfunction "11_11") (pintype "passive"))
      (node (ref "LD5") (pin "2") (pinfunction "A_2") (pintype "passive"))
      (node (ref "LD6") (pin "2") (pinfunction "A_2") (pintype "passive"))
      (node (ref "LD8") (pin "2") (pinfunction "A_2") (pintype "passive"))
      (node (ref "LD9") (pin "2") (pinfunction "A_2") (pintype "passive"))
      (node (ref "R114") (pin "2") (pinfunction "2_2") (pintype "passive"))
    )
    (net (code "44") (name "P3V3_MP") (class "Default")
      (node (ref "C96") (pin "2") (pinfunction "2_2") (pintype "passive"))
      (node (ref "IC30") (pin "8") (pinfunction "+VS_8") (pintype "power_in"))
      (node (ref "R121") (pin "1") (pinfunction "1_1") (pintype "passive"))
      (node (ref "R122") (pin "1") (pinfunction "1_1") (pintype "passive"))
      (node (ref "R123") (pin "1") (pinfunction "1_1") (pintype "passive"))
      (node (ref "R124") (pin "2") (pinfunction "2_2") (pintype "passive"))
      (node (ref "R125") (pin "2") (pinfunction "2_2") (pintype "passive"))
    )
    (net (code "45") (name "P12V0_SW") (class "Default")
      (node (ref "J5") (pin "10") (pinfunction "10_10") (pintype "passive"))
      (node (ref "J5") (pin "6") (pinfunction "6_6") (pintype "passive"))
      (node (ref "J5") (pin "8") (pinfunction "8_8") (pintype "passive"))
    )
    (net (code "46") (name "unconnected-(D10-I{slash}O1-Pad1)") (class "Default")
      (node (ref "D10") (pin "1") (pinfunction "I/O1_1") (pintype "bidirectional+no_connect"))
    )
    (net (code "47") (name "unconnected-(D10-I{slash}O4-Pad6)") (class "Default")
      (node (ref "D10") (pin "6") (pinfunction "I/O4_6") (pintype "bidirectional+no_connect"))
    )
    (net (code "48") (name "unconnected-(J5-Pad12)") (class "Default")
      (node (ref "J5") (pin "12") (pinfunction "12_12") (pintype "passive"))
    )
  )
)
